# timetracker-1-1.net
KiCad netlist of a schematic drawn in EAGLE
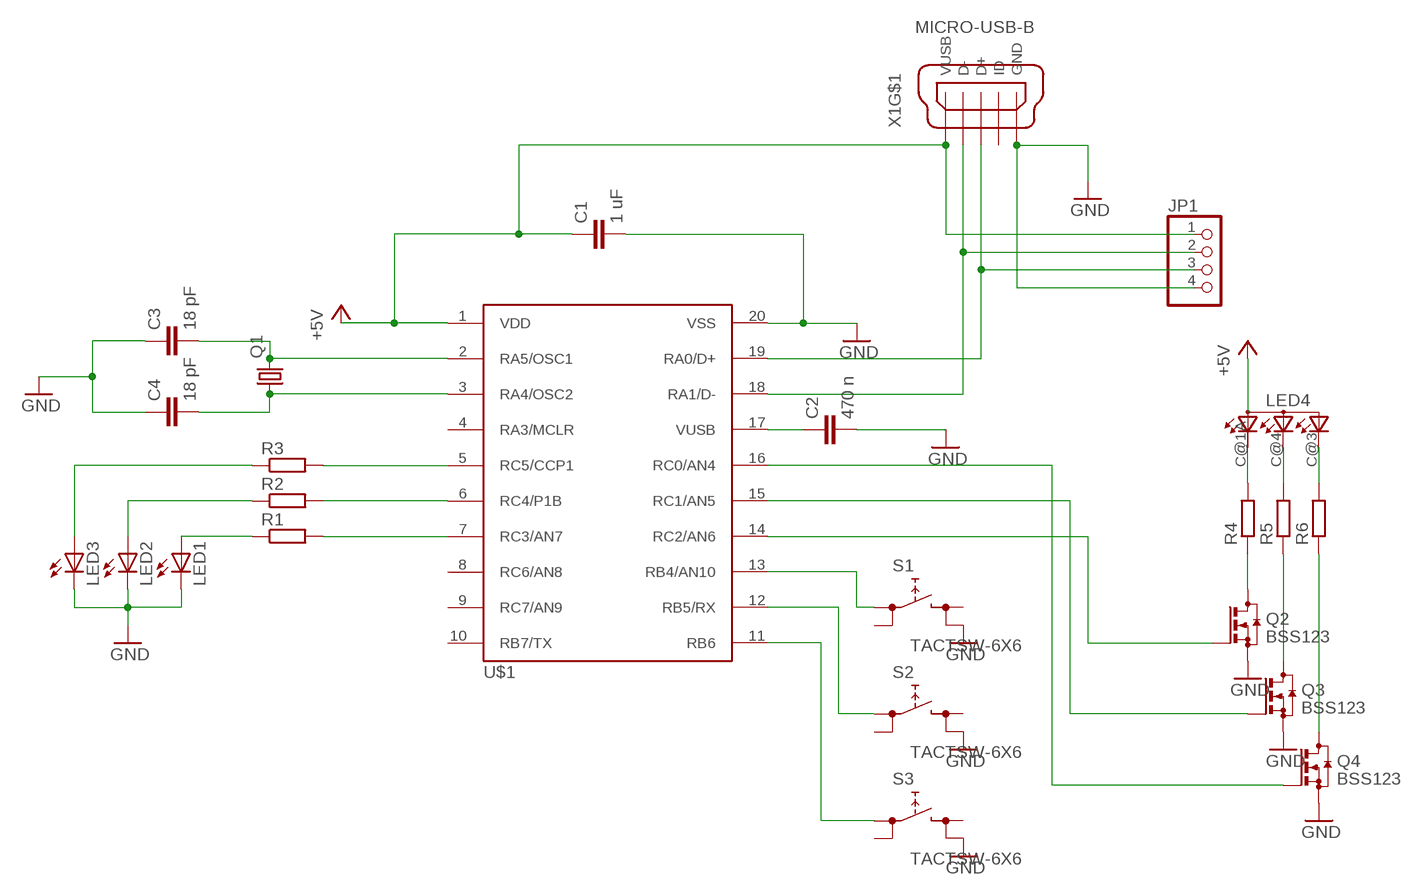
[diagram p0: schematic, sheet 1]

(export (version "E")
  (design (tool "Eeschema 10.0.6"))
  (components
    (comp (ref "C1")
      (value "1 uF")
      (footprint "eagle-import:C0805")
      (libsource (lib "eagle-import") (part "C-EUC0805"))
    )
    (comp (ref "C2")
      (value "470 n")
      (footprint "eagle-import:C0805")
      (libsource (lib "eagle-import") (part "C-EUC0805"))
    )
    (comp (ref "C3")
      (value "18 pF")
      (footprint "eagle-import:C0805")
      (libsource (lib "eagle-import") (part "C-EUC0805"))
    )
    (comp (ref "C4")
      (value "18 pF")
      (footprint "eagle-import:C0805")
      (libsource (lib "eagle-import") (part "C-EUC0805"))
    )
    (comp (ref "JP1")
      (value "PINHD-1X4")
      (footprint "eagle-import:1X04")
      (libsource (lib "eagle-import") (part "PINHD-1X4"))
    )
    (comp (ref "LED1")
      (value "LEDSML0805")
      (footprint "eagle-import:SML0805")
      (libsource (lib "eagle-import") (part "LEDSML0805"))
    )
    (comp (ref "LED2")
      (value "LEDSML0805")
      (footprint "eagle-import:SML0805")
      (libsource (lib "eagle-import") (part "LEDSML0805"))
    )
    (comp (ref "LED3")
      (value "LEDSML0805")
      (footprint "eagle-import:SML0805")
      (libsource (lib "eagle-import") (part "LEDSML0805"))
    )
    (comp (ref "LED4")
      (value "RGBLED-3P-LCC-4")
      (footprint "eagle-import:P-LCC-4")
      (libsource (lib "eagle-import") (part "RGBLED-3P-LCC-4"))
    )
    (comp (ref "Q1")
      (value "CRYSTALHC49UP")
      (footprint "eagle-import:HC49UP")
      (libsource (lib "eagle-import") (part "CRYSTALHC49UP"))
    )
    (comp (ref "Q2")
      (value "BSS123")
      (footprint "eagle-import:SOT23")
      (libsource (lib "eagle-import") (part "BSS123"))
    )
    (comp (ref "Q3")
      (value "BSS123")
      (footprint "eagle-import:SOT23")
      (libsource (lib "eagle-import") (part "BSS123"))
    )
    (comp (ref "Q4")
      (value "BSS123")
      (footprint "eagle-import:SOT23")
      (libsource (lib "eagle-import") (part "BSS123"))
    )
    (comp (ref "R1")
      (value "R-EU_R0805")
      (footprint "eagle-import:R0805")
      (libsource (lib "eagle-import") (part "R-EU_R0805"))
    )
    (comp (ref "R2")
      (value "R-EU_R0805")
      (footprint "eagle-import:R0805")
      (libsource (lib "eagle-import") (part "R-EU_R0805"))
    )
    (comp (ref "R3")
      (value "R-EU_R0805")
      (footprint "eagle-import:R0805")
      (libsource (lib "eagle-import") (part "R-EU_R0805"))
    )
    (comp (ref "R4")
      (value "R-EU_R0805")
      (footprint "eagle-import:R0805")
      (libsource (lib "eagle-import") (part "R-EU_R0805"))
    )
    (comp (ref "R5")
      (value "R-EU_R0805")
      (footprint "eagle-import:R0805")
      (libsource (lib "eagle-import") (part "R-EU_R0805"))
    )
    (comp (ref "R6")
      (value "R-EU_R0805")
      (footprint "eagle-import:R0805")
      (libsource (lib "eagle-import") (part "R-EU_R0805"))
    )
    (comp (ref "S1")
      (value "TACTSW-6X6")
      (footprint "eagle-import:TACTSW-6X6")
      (libsource (lib "eagle-import") (part "TACTSW-6X6"))
    )
    (comp (ref "S2")
      (value "TACTSW-6X6")
      (footprint "eagle-import:TACTSW-6X6")
      (libsource (lib "eagle-import") (part "TACTSW-6X6"))
    )
    (comp (ref "S3")
      (value "TACTSW-6X6")
      (footprint "eagle-import:TACTSW-6X6")
      (libsource (lib "eagle-import") (part "TACTSW-6X6"))
    )
    (comp (ref "U$1")
      (value "PIC18F14K50")
      (footprint "eagle-import:DIL20")
      (libsource (lib "eagle-import") (part "PIC18F14K50"))
    )
    (comp (ref "X1")
      (value "MICRO-USB-B")
      (footprint "eagle-import:MICRO-B-PAC")
      (libsource (lib "eagle-import") (part "MICRO-USB-B"))
    )
  )
  (nets
    (net (code "1") (name "+5V") (class "Default")
      (node (ref "C1") (pin "1") (pinfunction "1_1") (pintype "passive"))
      (node (ref "JP1") (pin "1") (pinfunction "1_1") (pintype "passive"))
      (node (ref "LED4") (pin "A") (pinfunction "A2_A") (pintype "passive"))
      (node (ref "U$1") (pin "1") (pinfunction "VDD_1") (pintype "bidirectional"))
      (node (ref "X1") (pin "1") (pinfunction "VUSB_1") (pintype "passive"))
    )
    (net (code "2") (name "GND") (class "Default")
      (node (ref "C1") (pin "2") (pinfunction "2_2") (pintype "passive"))
      (node (ref "C2") (pin "2") (pinfunction "2_2") (pintype "passive"))
      (node (ref "C3") (pin "1") (pinfunction "1_1") (pintype "passive"))
      (node (ref "C4") (pin "1") (pinfunction "1_1") (pintype "passive"))
      (node (ref "JP1") (pin "4") (pinfunction "4_4") (pintype "passive"))
      (node (ref "LED1") (pin "C") (pinfunction "C_C") (pintype "passive"))
      (node (ref "LED2") (pin "C") (pinfunction "C_C") (pintype "passive"))
      (node (ref "LED3") (pin "C") (pinfunction "C_C") (pintype "passive"))
      (node (ref "Q2") (pin "2") (pinfunction "S_2") (pintype "passive"))
      (node (ref "Q3") (pin "2") (pinfunction "S_2") (pintype "passive"))
      (node (ref "Q4") (pin "2") (pinfunction "S_2") (pintype "passive"))
      (node (ref "S1") (pin "4") (pinfunction "2.2_4") (pintype "passive"))
      (node (ref "S2") (pin "4") (pinfunction "2.2_4") (pintype "passive"))
      (node (ref "S3") (pin "4") (pinfunction "2.2_4") (pintype "passive"))
      (node (ref "U$1") (pin "20") (pinfunction "VSS_20") (pintype "bidirectional"))
      (node (ref "X1") (pin "5") (pinfunction "GND_5") (pintype "passive"))
    )
    (net (code "3") (name "Net-(LED1-PadA)") (class "Default")
      (node (ref "LED1") (pin "A") (pinfunction "A_A") (pintype "passive"))
      (node (ref "R1") (pin "1") (pinfunction "1_1") (pintype "passive"))
    )
    (net (code "4") (name "Net-(LED2-PadA)") (class "Default")
      (node (ref "LED2") (pin "A") (pinfunction "A_A") (pintype "passive"))
      (node (ref "R2") (pin "1") (pinfunction "1_1") (pintype "passive"))
    )
    (net (code "5") (name "Net-(LED3-PadA)") (class "Default")
      (node (ref "LED3") (pin "A") (pinfunction "A_A") (pintype "passive"))
      (node (ref "R3") (pin "1") (pinfunction "1_1") (pintype "passive"))
    )
    (net (code "6") (name "Net-(LED4-CBLUE)") (class "Default")
      (node (ref "LED4") (pin "C@3") (pinfunction "CBLUE_C@3") (pintype "passive"))
      (node (ref "R6") (pin "2") (pinfunction "2_2") (pintype "passive"))
    )
    (net (code "7") (name "Net-(LED4-CGREEN)") (class "Default")
      (node (ref "LED4") (pin "C@4") (pinfunction "CGREEN_C@4") (pintype "passive"))
      (node (ref "R5") (pin "2") (pinfunction "2_2") (pintype "passive"))
    )
    (net (code "8") (name "Net-(LED4-CRED)") (class "Default")
      (node (ref "LED4") (pin "C@1") (pinfunction "CRED_C@1") (pintype "passive"))
      (node (ref "R4") (pin "2") (pinfunction "2_2") (pintype "passive"))
    )
    (net (code "9") (name "Net-(Q2-D)") (class "Default")
      (node (ref "Q2") (pin "3") (pinfunction "D_3") (pintype "passive"))
      (node (ref "R4") (pin "1") (pinfunction "1_1") (pintype "passive"))
    )
    (net (code "10") (name "Net-(Q2-G)") (class "Default")
      (node (ref "Q2") (pin "1") (pinfunction "G_1") (pintype "passive"))
      (node (ref "U$1") (pin "14") (pinfunction "RC2/AN6_14") (pintype "bidirectional"))
    )
    (net (code "11") (name "Net-(Q3-D)") (class "Default")
      (node (ref "Q3") (pin "3") (pinfunction "D_3") (pintype "passive"))
      (node (ref "R5") (pin "1") (pinfunction "1_1") (pintype "passive"))
    )
    (net (code "12") (name "Net-(Q3-G)") (class "Default")
      (node (ref "Q3") (pin "1") (pinfunction "G_1") (pintype "passive"))
      (node (ref "U$1") (pin "15") (pinfunction "RC1/AN5_15") (pintype "bidirectional"))
    )
    (net (code "13") (name "Net-(Q4-D)") (class "Default")
      (node (ref "Q4") (pin "3") (pinfunction "D_3") (pintype "passive"))
      (node (ref "R6") (pin "1") (pinfunction "1_1") (pintype "passive"))
    )
    (net (code "14") (name "Net-(Q4-G)") (class "Default")
      (node (ref "Q4") (pin "1") (pinfunction "G_1") (pintype "passive"))
      (node (ref "U$1") (pin "16") (pinfunction "RC0/AN4_16") (pintype "bidirectional"))
    )
    (net (code "15") (name "Net-(S1-1.1)") (class "Default")
      (node (ref "S1") (pin "1") (pinfunction "1.1_1") (pintype "passive"))
      (node (ref "U$1") (pin "13") (pinfunction "RB4/AN10_13") (pintype "bidirectional"))
    )
    (net (code "16") (name "Net-(S2-1.1)") (class "Default")
      (node (ref "S2") (pin "1") (pinfunction "1.1_1") (pintype "passive"))
      (node (ref "U$1") (pin "12") (pinfunction "RB5/RX_12") (pintype "bidirectional"))
    )
    (net (code "17") (name "Net-(S3-1.1)") (class "Default")
      (node (ref "S3") (pin "1") (pinfunction "1.1_1") (pintype "passive"))
      (node (ref "U$1") (pin "11") (pinfunction "RB6_11") (pintype "bidirectional"))
    )
    (net (code "18") (name "Net-(U$1-RA0{slash}D+)") (class "Default")
      (node (ref "JP1") (pin "3") (pinfunction "3_3") (pintype "passive"))
      (node (ref "U$1") (pin "19") (pinfunction "RA0/D+_19") (pintype "bidirectional"))
      (node (ref "X1") (pin "3") (pinfunction "D+_3") (pintype "passive"))
    )
    (net (code "19") (name "Net-(U$1-RA1{slash}D-)") (class "Default")
      (node (ref "JP1") (pin "2") (pinfunction "2_2") (pintype "passive"))
      (node (ref "U$1") (pin "18") (pinfunction "RA1/D-_18") (pintype "bidirectional"))
      (node (ref "X1") (pin "2") (pinfunction "D-_2") (pintype "passive"))
    )
    (net (code "20") (name "Net-(U$1-RA4{slash}OSC2)") (class "Default")
      (node (ref "C4") (pin "2") (pinfunction "2_2") (pintype "passive"))
      (node (ref "Q1") (pin "1") (pinfunction "1_1") (pintype "passive"))
      (node (ref "U$1") (pin "3") (pinfunction "RA4/OSC2_3") (pintype "bidirectional"))
    )
    (net (code "21") (name "Net-(U$1-RA5{slash}OSC1)") (class "Default")
      (node (ref "C3") (pin "2") (pinfunction "2_2") (pintype "passive"))
      (node (ref "Q1") (pin "2") (pinfunction "2_2") (pintype "passive"))
      (node (ref "U$1") (pin "2") (pinfunction "RA5/OSC1_2") (pintype "bidirectional"))
    )
    (net (code "22") (name "Net-(U$1-RC3{slash}AN7)") (class "Default")
      (node (ref "R1") (pin "2") (pinfunction "2_2") (pintype "passive"))
      (node (ref "U$1") (pin "7") (pinfunction "RC3/AN7_7") (pintype "bidirectional"))
    )
    (net (code "23") (name "Net-(U$1-RC4{slash}P1B)") (class "Default")
      (node (ref "R2") (pin "2") (pinfunction "2_2") (pintype "passive"))
      (node (ref "U$1") (pin "6") (pinfunction "RC4/P1B_6") (pintype "bidirectional"))
    )
    (net (code "24") (name "Net-(U$1-RC5{slash}CCP1)") (class "Default")
      (node (ref "R3") (pin "2") (pinfunction "2_2") (pintype "passive"))
      (node (ref "U$1") (pin "5") (pinfunction "RC5/CCP1_5") (pintype "bidirectional"))
    )
    (net (code "25") (name "Net-(U$1-VUSB)") (class "Default")
      (node (ref "C2") (pin "1") (pinfunction "1_1") (pintype "passive"))
      (node (ref "U$1") (pin "17") (pinfunction "VUSB_17") (pintype "bidirectional"))
    )
    (net (code "26") (name "unconnected-(S1-1.2-Pad2)") (class "Default")
      (node (ref "S1") (pin "2") (pinfunction "1.2_2") (pintype "passive"))
    )
    (net (code "27") (name "unconnected-(S1-2.1-Pad3)") (class "Default")
      (node (ref "S1") (pin "3") (pinfunction "2.1_3") (pintype "passive"))
    )
    (net (code "28") (name "unconnected-(S2-1.2-Pad2)") (class "Default")
      (node (ref "S2") (pin "2") (pinfunction "1.2_2") (pintype "passive"))
    )
    (net (code "29") (name "unconnected-(S2-2.1-Pad3)") (class "Default")
      (node (ref "S2") (pin "3") (pinfunction "2.1_3") (pintype "passive"))
    )
    (net (code "30") (name "unconnected-(S3-1.2-Pad2)") (class "Default")
      (node (ref "S3") (pin "2") (pinfunction "1.2_2") (pintype "passive"))
    )
    (net (code "31") (name "unconnected-(S3-2.1-Pad3)") (class "Default")
      (node (ref "S3") (pin "3") (pinfunction "2.1_3") (pintype "passive"))
    )
    (net (code "32") (name "unconnected-(U$1-RA3{slash}MCLR-Pad4)") (class "Default")
      (node (ref "U$1") (pin "4") (pinfunction "RA3/MCLR_4") (pintype "bidirectional"))
    )
    (net (code "33") (name "unconnected-(U$1-RB7{slash}TX-Pad10)") (class "Default")
      (node (ref "U$1") (pin "10") (pinfunction "RB7/TX_10") (pintype "bidirectional"))
    )
    (net (code "34") (name "unconnected-(U$1-RC6{slash}AN8-Pad8)") (class "Default")
      (node (ref "U$1") (pin "8") (pinfunction "RC6/AN8_8") (pintype "bidirectional"))
    )
    (net (code "35") (name "unconnected-(U$1-RC7{slash}AN9-Pad9)") (class "Default")
      (node (ref "U$1") (pin "9") (pinfunction "RC7/AN9_9") (pintype "bidirectional"))
    )
    (net (code "36") (name "unconnected-(X1A-ID-Pad4)") (class "Default")
      (node (ref "X1") (pin "4") (pinfunction "ID_4") (pintype "passive"))
    )
  )
)
